# arcie.net
KiCad netlist of a schematic drawn in EAGLE
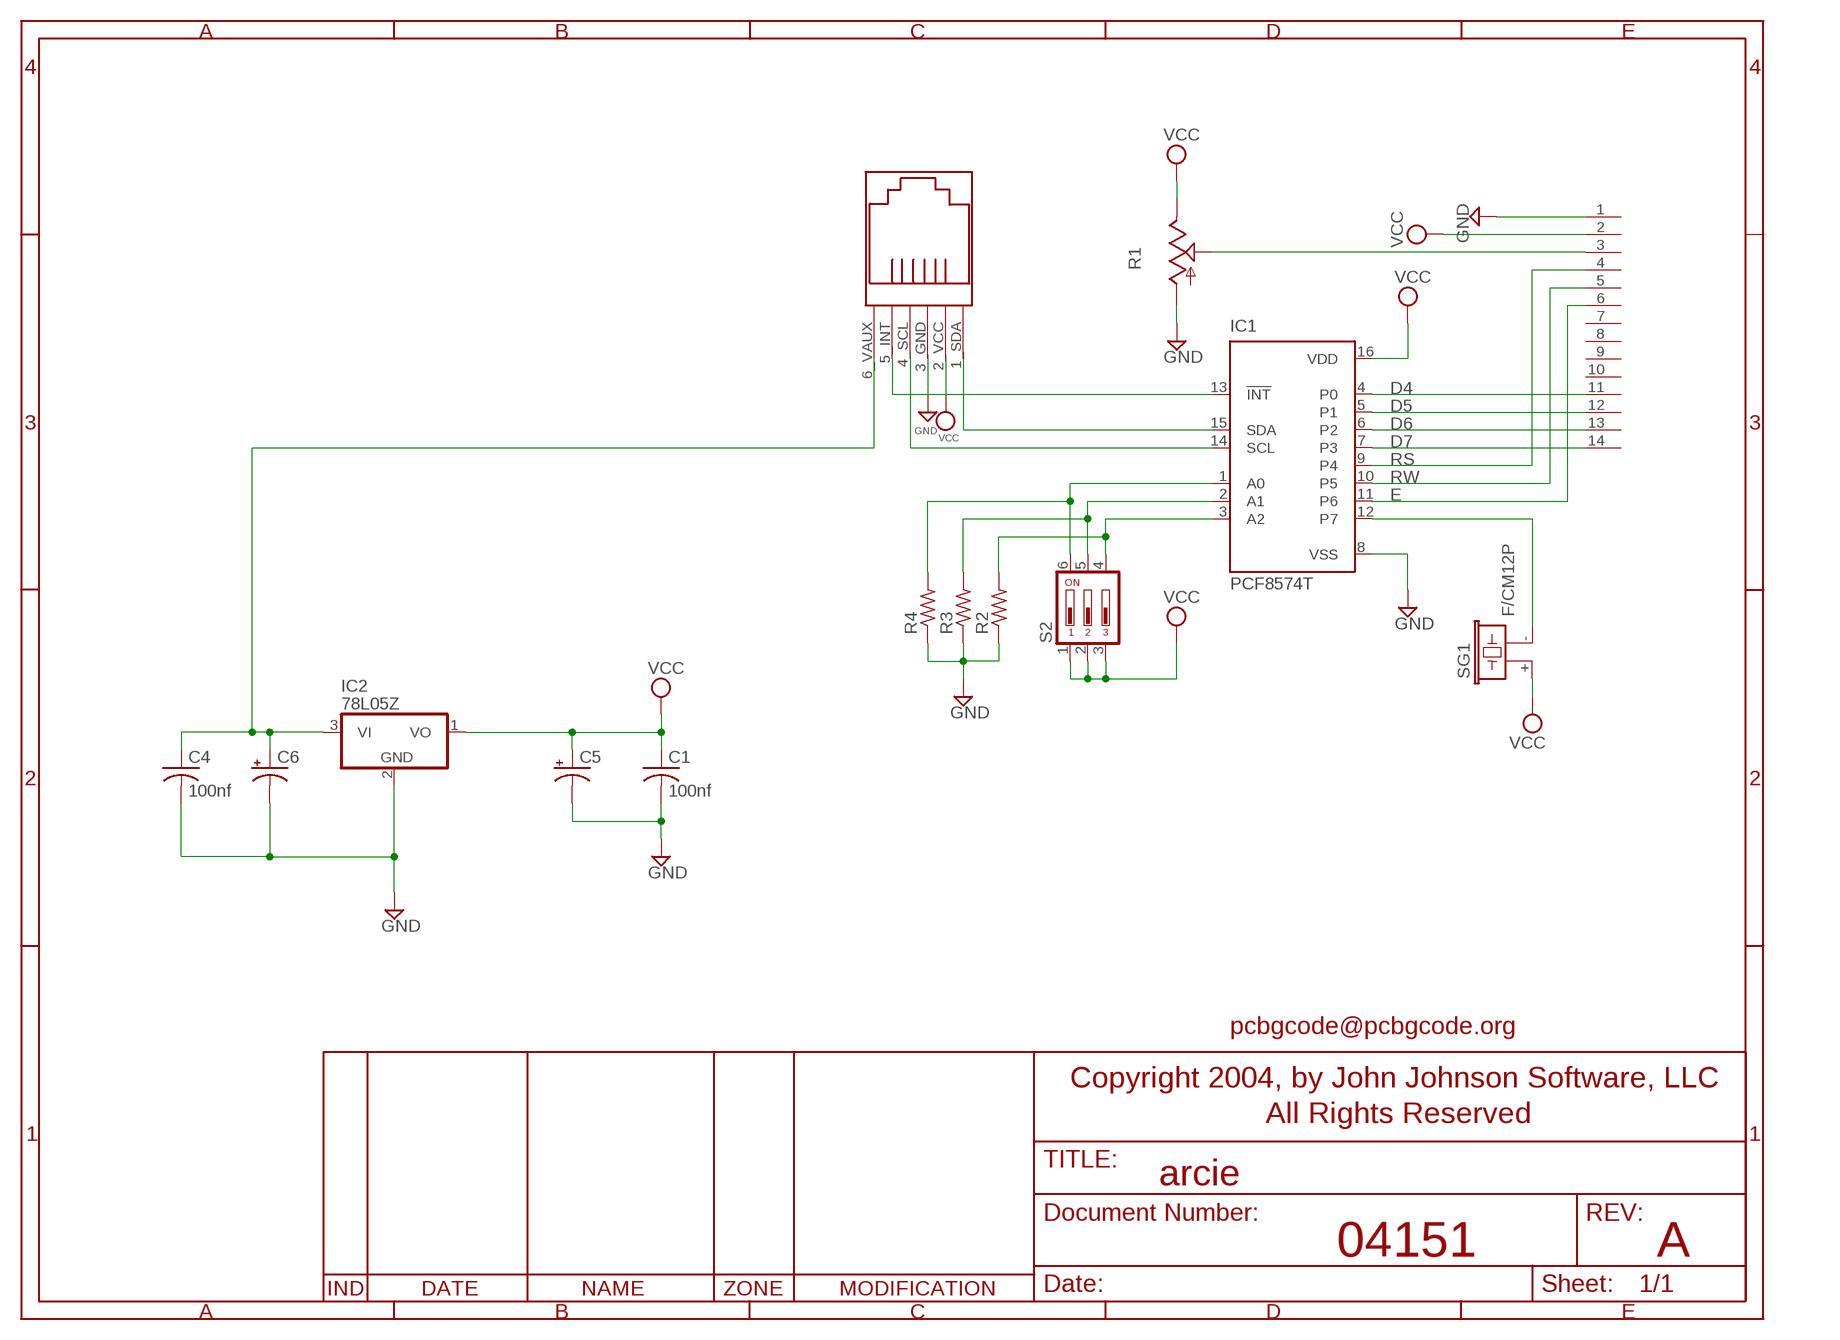
[diagram p0: schematic, sheet 1]

(export (version "E")
  (design (tool "Eeschema 10.0.6"))
  (components
    (comp (ref "C1")
      (value "100nf")
      (footprint "eagle-import:C1206")
      (libsource (lib "eagle-import") (part "C-USC1206"))
    )
    (comp (ref "C4")
      (value "100nf")
      (footprint "eagle-import:C1206")
      (libsource (lib "eagle-import") (part "C-USC1206"))
    )
    (comp (ref "C5")
      (value "CPOL-US!FAT_E2,5-5")
      (footprint "eagle-import:!FAT_E2,5-5")
      (libsource (lib "eagle-import") (part "CPOL-US!FAT_E2,5-5"))
    )
    (comp (ref "C6")
      (value "CPOL-US!FAT_E2,5-5")
      (footprint "eagle-import:!FAT_E2,5-5")
      (libsource (lib "eagle-import") (part "CPOL-US!FAT_E2,5-5"))
    )
    (comp (ref "IC1")
      (value "PCF8574T")
      (footprint "eagle-import:SO16W")
      (libsource (lib "eagle-import") (part "PCF8574T"))
    )
    (comp (ref "IC2")
      (value "78L05Z")
      (footprint "eagle-import:TO92")
      (libsource (lib "eagle-import") (part "78ZL05"))
    )
    (comp (ref "R1")
      (value "TRIM_US-PT-SPIN")
      (footprint "eagle-import:PT-SPIN")
      (libsource (lib "eagle-import") (part "TRIM_US-PT-SPIN"))
    )
    (comp (ref "R2")
      (value "R-US_R1206")
      (footprint "eagle-import:R1206")
      (libsource (lib "eagle-import") (part "R-US_R1206"))
    )
    (comp (ref "R3")
      (value "R-US_R1206")
      (footprint "eagle-import:R1206")
      (libsource (lib "eagle-import") (part "R-US_R1206"))
    )
    (comp (ref "R4")
      (value "R-US_R1206")
      (footprint "eagle-import:R1206")
      (libsource (lib "eagle-import") (part "R-US_R1206"))
    )
    (comp (ref "S2")
      (value "DIP03YL")
      (footprint "eagle-import:DIP03YL")
      (libsource (lib "eagle-import") (part "DIP03YL"))
    )
    (comp (ref "SG1")
      (value "F/CM12P")
      (footprint "eagle-import:F_CM12P")
      (libsource (lib "eagle-import") (part "F/CM12P"))
    )
    (comp (ref "U$1")
      (value "RJ-12")
      (footprint "eagle-import:RJ-12")
      (libsource (lib "eagle-import") (part "RJ-12"))
    )
    (comp (ref "U$2")
      (value "MA07-2-SGL")
      (footprint "eagle-import:MA07-2")
      (libsource (lib "eagle-import") (part "MA07-2-SGL"))
    )
  )
  (nets
    (net (code "1") (name "/D4") (class "Default")
      (node (ref "IC1") (pin "4") (pinfunction "P0_4") (pintype "bidirectional"))
      (node (ref "U$2") (pin "11") (pinfunction "11_11") (pintype "passive"))
    )
    (net (code "2") (name "/D5") (class "Default")
      (node (ref "IC1") (pin "5") (pinfunction "P1_5") (pintype "bidirectional"))
      (node (ref "U$2") (pin "12") (pinfunction "12_12") (pintype "passive"))
    )
    (net (code "3") (name "/D6") (class "Default")
      (node (ref "IC1") (pin "6") (pinfunction "P2_6") (pintype "bidirectional"))
      (node (ref "U$2") (pin "13") (pinfunction "13_13") (pintype "passive"))
    )
    (net (code "4") (name "/D7") (class "Default")
      (node (ref "IC1") (pin "7") (pinfunction "P3_7") (pintype "bidirectional"))
      (node (ref "U$2") (pin "14") (pinfunction "14_14") (pintype "passive"))
    )
    (net (code "5") (name "/E") (class "Default")
      (node (ref "IC1") (pin "11") (pinfunction "P6_11") (pintype "bidirectional"))
      (node (ref "U$2") (pin "6") (pinfunction "6_6") (pintype "passive"))
    )
    (net (code "6") (name "/RS") (class "Default")
      (node (ref "IC1") (pin "9") (pinfunction "P4_9") (pintype "bidirectional"))
      (node (ref "U$2") (pin "4") (pinfunction "4_4") (pintype "passive"))
    )
    (net (code "7") (name "/RW") (class "Default")
      (node (ref "IC1") (pin "10") (pinfunction "P5_10") (pintype "bidirectional"))
      (node (ref "U$2") (pin "5") (pinfunction "5_5") (pintype "passive"))
    )
    (net (code "8") (name "GND") (class "Default")
      (node (ref "C1") (pin "2") (pinfunction "2_2") (pintype "passive"))
      (node (ref "C4") (pin "2") (pinfunction "2_2") (pintype "passive"))
      (node (ref "C5") (pin "P$2") (pinfunction "-_P$2") (pintype "passive"))
      (node (ref "C6") (pin "P$2") (pinfunction "-_P$2") (pintype "passive"))
      (node (ref "IC1") (pin "8") (pinfunction "VSS_8") (pintype "power_in"))
      (node (ref "IC2") (pin "2") (pinfunction "GND_2") (pintype "passive"))
      (node (ref "R1") (pin "A") (pinfunction "A_A") (pintype "passive"))
      (node (ref "R2") (pin "1") (pinfunction "1_1") (pintype "passive"))
      (node (ref "R3") (pin "1") (pinfunction "1_1") (pintype "passive"))
      (node (ref "R4") (pin "1") (pinfunction "1_1") (pintype "passive"))
      (node (ref "U$1") (pin "3_GND") (pinfunction "3_GND_3_GND") (pintype "bidirectional"))
      (node (ref "U$2") (pin "1") (pinfunction "1_1") (pintype "passive"))
    )
    (net (code "9") (name "Net-(C6-+)") (class "Default")
      (node (ref "C4") (pin "1") (pinfunction "1_1") (pintype "passive"))
      (node (ref "C6") (pin "P$1") (pinfunction "+_P$1") (pintype "passive"))
      (node (ref "IC2") (pin "3") (pinfunction "VI_3") (pintype "input"))
      (node (ref "U$1") (pin "6_VAUX") (pinfunction "6_VAUX_6_VAUX") (pintype "bidirectional"))
    )
    (net (code "10") (name "Net-(IC1-A0)") (class "Default")
      (node (ref "IC1") (pin "1") (pinfunction "A0_1") (pintype "input"))
      (node (ref "R4") (pin "2") (pinfunction "2_2") (pintype "passive"))
      (node (ref "S2") (pin "6") (pinfunction "6_6") (pintype "passive"))
    )
    (net (code "11") (name "Net-(IC1-A1)") (class "Default")
      (node (ref "IC1") (pin "2") (pinfunction "A1_2") (pintype "input"))
      (node (ref "R3") (pin "2") (pinfunction "2_2") (pintype "passive"))
      (node (ref "S2") (pin "5") (pinfunction "5_5") (pintype "passive"))
    )
    (net (code "12") (name "Net-(IC1-A2)") (class "Default")
      (node (ref "IC1") (pin "3") (pinfunction "A2_3") (pintype "input"))
      (node (ref "R2") (pin "2") (pinfunction "2_2") (pintype "passive"))
      (node (ref "S2") (pin "4") (pinfunction "4_4") (pintype "passive"))
    )
    (net (code "13") (name "Net-(IC1-P7)") (class "Default")
      (node (ref "IC1") (pin "12") (pinfunction "P7_12") (pintype "bidirectional"))
      (node (ref "SG1") (pin "-") (pinfunction "2_-") (pintype "passive"))
    )
    (net (code "14") (name "Net-(IC1-SCL)") (class "Default")
      (node (ref "IC1") (pin "14") (pinfunction "SCL_14") (pintype "input"))
      (node (ref "U$1") (pin "4_SCL") (pinfunction "4_SCL_4_SCL") (pintype "bidirectional"))
    )
    (net (code "15") (name "Net-(IC1-SDA)") (class "Default")
      (node (ref "IC1") (pin "15") (pinfunction "SDA_15") (pintype "bidirectional"))
      (node (ref "U$1") (pin "1_SDA") (pinfunction "1_SDA_1_SDA") (pintype "bidirectional"))
    )
    (net (code "16") (name "Net-(IC1-~{INT})") (class "Default")
      (node (ref "IC1") (pin "13") (pinfunction "~{INT}_13") (pintype "output"))
      (node (ref "U$1") (pin "5_INT") (pinfunction "5_INT_5_INT") (pintype "bidirectional"))
    )
    (net (code "17") (name "Net-(R1-PadS)") (class "Default")
      (node (ref "R1") (pin "S") (pinfunction "S_S") (pintype "passive"))
      (node (ref "U$2") (pin "3") (pinfunction "3_3") (pintype "passive"))
    )
    (net (code "18") (name "VCC") (class "Default")
      (node (ref "C1") (pin "1") (pinfunction "1_1") (pintype "passive"))
      (node (ref "C5") (pin "P$1") (pinfunction "+_P$1") (pintype "passive"))
      (node (ref "IC1") (pin "16") (pinfunction "VDD_16") (pintype "power_in"))
      (node (ref "IC2") (pin "1") (pinfunction "VO_1") (pintype "passive"))
      (node (ref "R1") (pin "E") (pinfunction "E_E") (pintype "passive"))
      (node (ref "S2") (pin "1") (pinfunction "1_1") (pintype "passive"))
      (node (ref "S2") (pin "2") (pinfunction "2_2") (pintype "passive"))
      (node (ref "S2") (pin "3") (pinfunction "3_3") (pintype "passive"))
      (node (ref "SG1") (pin "+") (pinfunction "1_+") (pintype "passive"))
      (node (ref "U$1") (pin "2_VCC") (pinfunction "2_VCC_2_VCC") (pintype "bidirectional"))
      (node (ref "U$2") (pin "2") (pinfunction "2_2") (pintype "passive"))
    )
    (net (code "19") (name "unconnected-(U$2-Pad7)") (class "Default")
      (node (ref "U$2") (pin "7") (pinfunction "7_7") (pintype "passive"))
    )
    (net (code "20") (name "unconnected-(U$2-Pad8)") (class "Default")
      (node (ref "U$2") (pin "8") (pinfunction "8_8") (pintype "passive"))
    )
    (net (code "21") (name "unconnected-(U$2-Pad9)") (class "Default")
      (node (ref "U$2") (pin "9") (pinfunction "9_9") (pintype "passive"))
    )
    (net (code "22") (name "unconnected-(U$2-Pad10)") (class "Default")
      (node (ref "U$2") (pin "10") (pinfunction "10_10") (pintype "passive"))
    )
  )
)
